# nixie_temp_clock.net
KiCad netlist of a schematic drawn in EAGLE
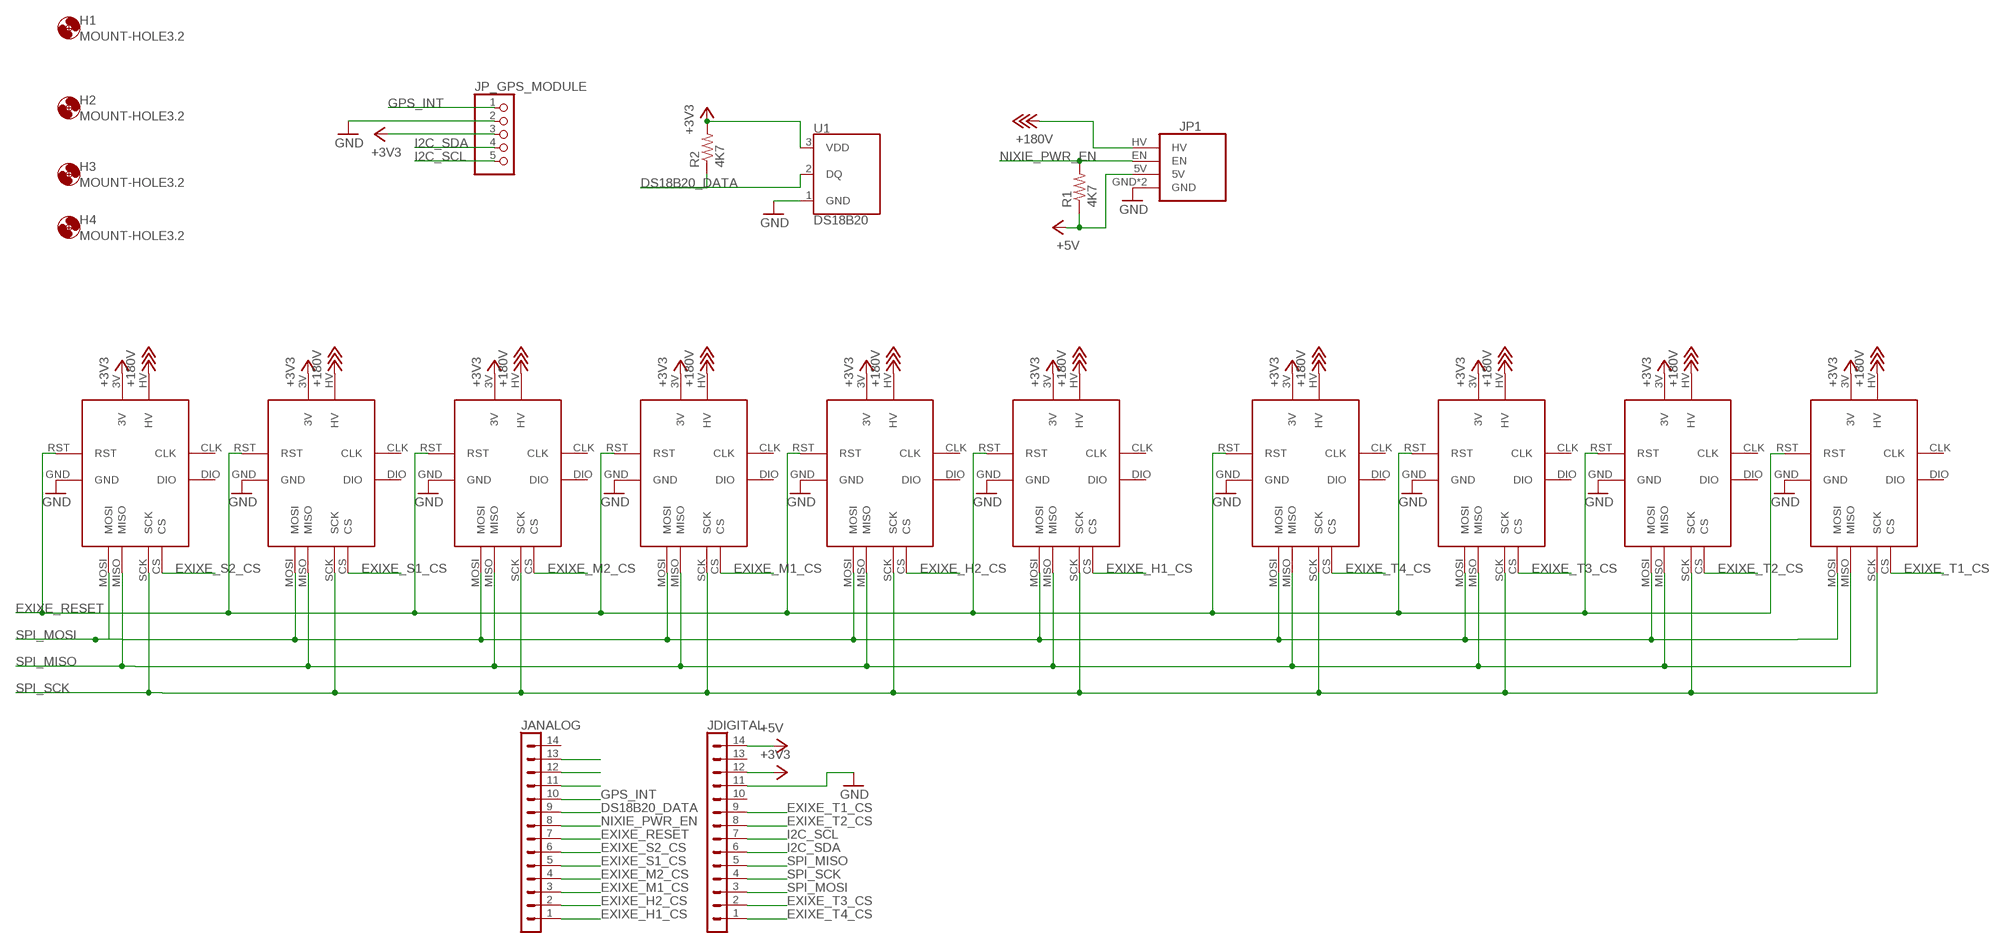
[diagram p0: schematic, sheet 1]

(export (version "E")
  (design (tool "Eeschema 10.0.6"))
  (components
    (comp (ref "EXIXE_H1")
      (value "EXIXE_MODULE_EXIXE")
      (footprint "eagle-import:EXIXE_MODULE_EXIXE_PAC")
      (libsource (lib "eagle-import") (part "EXIXE_MODULE_EXIXE"))
    )
    (comp (ref "EXIXE_H2")
      (value "EXIXE_MODULE_EXIXE")
      (footprint "eagle-import:EXIXE_MODULE_EXIXE_PAC")
      (libsource (lib "eagle-import") (part "EXIXE_MODULE_EXIXE"))
    )
    (comp (ref "EXIXE_M1")
      (value "EXIXE_MODULE_EXIXE")
      (footprint "eagle-import:EXIXE_MODULE_EXIXE_PAC")
      (libsource (lib "eagle-import") (part "EXIXE_MODULE_EXIXE"))
    )
    (comp (ref "EXIXE_M2")
      (value "EXIXE_MODULE_EXIXE")
      (footprint "eagle-import:EXIXE_MODULE_EXIXE_PAC")
      (libsource (lib "eagle-import") (part "EXIXE_MODULE_EXIXE"))
    )
    (comp (ref "EXIXE_S1")
      (value "EXIXE_MODULE_EXIXE")
      (footprint "eagle-import:EXIXE_MODULE_EXIXE_PAC")
      (libsource (lib "eagle-import") (part "EXIXE_MODULE_EXIXE"))
    )
    (comp (ref "EXIXE_S2")
      (value "EXIXE_MODULE_EXIXE")
      (footprint "eagle-import:EXIXE_MODULE_EXIXE_PAC")
      (libsource (lib "eagle-import") (part "EXIXE_MODULE_EXIXE"))
    )
    (comp (ref "EXIXE_T1")
      (value "EXIXE_MODULE_EXIXE")
      (footprint "eagle-import:EXIXE_MODULE_EXIXE_PAC")
      (libsource (lib "eagle-import") (part "EXIXE_MODULE_EXIXE"))
    )
    (comp (ref "EXIXE_T2")
      (value "EXIXE_MODULE_EXIXE")
      (footprint "eagle-import:EXIXE_MODULE_EXIXE_PAC")
      (libsource (lib "eagle-import") (part "EXIXE_MODULE_EXIXE"))
    )
    (comp (ref "EXIXE_T3")
      (value "EXIXE_MODULE_EXIXE")
      (footprint "eagle-import:EXIXE_MODULE_EXIXE_PAC")
      (libsource (lib "eagle-import") (part "EXIXE_MODULE_EXIXE"))
    )
    (comp (ref "EXIXE_T4")
      (value "EXIXE_MODULE_EXIXE")
      (footprint "eagle-import:EXIXE_MODULE_EXIXE_PAC")
      (libsource (lib "eagle-import") (part "EXIXE_MODULE_EXIXE"))
    )
    (comp (ref "H1")
      (value "MOUNT-HOLE3.2")
      (footprint "eagle-import:3,2")
      (libsource (lib "eagle-import") (part "MOUNT-HOLE3.2"))
    )
    (comp (ref "H2")
      (value "MOUNT-HOLE3.2")
      (footprint "eagle-import:3,2")
      (libsource (lib "eagle-import") (part "MOUNT-HOLE3.2"))
    )
    (comp (ref "H3")
      (value "MOUNT-HOLE3.2")
      (footprint "eagle-import:3,2")
      (libsource (lib "eagle-import") (part "MOUNT-HOLE3.2"))
    )
    (comp (ref "H4")
      (value "MOUNT-HOLE3.2")
      (footprint "eagle-import:3,2")
      (libsource (lib "eagle-import") (part "MOUNT-HOLE3.2"))
    )
    (comp (ref "JANALOG")
      (value "ARDUINO-CONNECTORS_PINHD-1X14-SMTH")
      (footprint "eagle-import:ARDUINO-CONNECTORS_1X14")
      (fields (field (name "MANUFACTURER") "ELDECO"))
      (libsource (lib "eagle-import") (part "ARDUINO-CONNECTORS_PINHD-1X14-SMTH"))
    )
    (comp (ref "JDIGITAL")
      (value "ARDUINO-CONNECTORS_PINHD-1X14-SMTH")
      (footprint "eagle-import:ARDUINO-CONNECTORS_1X14")
      (fields (field (name "MANUFACTURER") "ELDECO"))
      (libsource (lib "eagle-import") (part "ARDUINO-CONNECTORS_PINHD-1X14-SMTH"))
    )
    (comp (ref "JP1")
      (value "EBAY_MODULETAOBAO")
      (footprint "eagle-import:TAOBAO_PKG")
      (libsource (lib "eagle-import") (part "EBAY_MODULETAOBAO"))
    )
    (comp (ref "JP_GPS_MODULE")
      (value "PINHD-1X5")
      (footprint "eagle-import:1X05")
      (libsource (lib "eagle-import") (part "PINHD-1X5"))
    )
    (comp (ref "R1")
      (value "4K7")
      (footprint "eagle-import:0207_15")
      (libsource (lib "eagle-import") (part "R-US_0207/15"))
    )
    (comp (ref "R2")
      (value "4K7")
      (footprint "eagle-import:0207_15")
      (libsource (lib "eagle-import") (part "R-US_0207/15"))
    )
    (comp (ref "U1")
      (value "DS18B20")
      (footprint "eagle-import:TO-92-AMMO")
      (libsource (lib "eagle-import") (part "DS18B20"))
    )
  )
  (nets
    (net (code "1") (name "+3V3") (class "Default")
      (node (ref "EXIXE_H1") (pin "3V") (pinfunction "3V_3V") (pintype "bidirectional"))
      (node (ref "EXIXE_H2") (pin "3V") (pinfunction "3V_3V") (pintype "bidirectional"))
      (node (ref "EXIXE_M1") (pin "3V") (pinfunction "3V_3V") (pintype "bidirectional"))
      (node (ref "EXIXE_M2") (pin "3V") (pinfunction "3V_3V") (pintype "bidirectional"))
      (node (ref "EXIXE_S1") (pin "3V") (pinfunction "3V_3V") (pintype "bidirectional"))
      (node (ref "EXIXE_S2") (pin "3V") (pinfunction "3V_3V") (pintype "bidirectional"))
      (node (ref "EXIXE_T1") (pin "3V") (pinfunction "3V_3V") (pintype "bidirectional"))
      (node (ref "EXIXE_T2") (pin "3V") (pinfunction "3V_3V") (pintype "bidirectional"))
      (node (ref "EXIXE_T3") (pin "3V") (pinfunction "3V_3V") (pintype "bidirectional"))
      (node (ref "EXIXE_T4") (pin "3V") (pinfunction "3V_3V") (pintype "bidirectional"))
      (node (ref "JDIGITAL") (pin "12") (pinfunction "12_12") (pintype "passive"))
      (node (ref "JP_GPS_MODULE") (pin "3") (pinfunction "3_3") (pintype "passive"))
      (node (ref "R2") (pin "2") (pinfunction "2_2") (pintype "passive"))
      (node (ref "U1") (pin "3") (pinfunction "VDD_3") (pintype "power_in"))
    )
    (net (code "2") (name "+5V") (class "Default")
      (node (ref "JDIGITAL") (pin "14") (pinfunction "14_14") (pintype "passive"))
      (node (ref "JP1") (pin "5V") (pinfunction "5V_5V") (pintype "bidirectional"))
      (node (ref "R1") (pin "1") (pinfunction "1_1") (pintype "passive"))
    )
    (net (code "3") (name "+180V") (class "Default")
      (node (ref "EXIXE_H1") (pin "HV") (pinfunction "HV_HV") (pintype "bidirectional"))
      (node (ref "EXIXE_H2") (pin "HV") (pinfunction "HV_HV") (pintype "bidirectional"))
      (node (ref "EXIXE_M1") (pin "HV") (pinfunction "HV_HV") (pintype "bidirectional"))
      (node (ref "EXIXE_M2") (pin "HV") (pinfunction "HV_HV") (pintype "bidirectional"))
      (node (ref "EXIXE_S1") (pin "HV") (pinfunction "HV_HV") (pintype "bidirectional"))
      (node (ref "EXIXE_S2") (pin "HV") (pinfunction "HV_HV") (pintype "bidirectional"))
      (node (ref "EXIXE_T1") (pin "HV") (pinfunction "HV_HV") (pintype "bidirectional"))
      (node (ref "EXIXE_T2") (pin "HV") (pinfunction "HV_HV") (pintype "bidirectional"))
      (node (ref "EXIXE_T3") (pin "HV") (pinfunction "HV_HV") (pintype "bidirectional"))
      (node (ref "EXIXE_T4") (pin "HV") (pinfunction "HV_HV") (pintype "bidirectional"))
      (node (ref "JP1") (pin "HV") (pinfunction "HV_HV") (pintype "bidirectional"))
    )
    (net (code "4") (name "/DS18B20_DATA") (class "Default")
      (node (ref "JANALOG") (pin "9") (pinfunction "9_9") (pintype "passive"))
      (node (ref "R2") (pin "1") (pinfunction "1_1") (pintype "passive"))
      (node (ref "U1") (pin "2") (pinfunction "DQ_2") (pintype "bidirectional"))
    )
    (net (code "5") (name "/EXIXE_H1_CS") (class "Default")
      (node (ref "EXIXE_S2") (pin "CS") (pinfunction "CS_CS") (pintype "bidirectional"))
      (node (ref "JANALOG") (pin "1") (pinfunction "1_1") (pintype "passive"))
    )
    (net (code "6") (name "/EXIXE_H2_CS") (class "Default")
      (node (ref "EXIXE_S1") (pin "CS") (pinfunction "CS_CS") (pintype "bidirectional"))
      (node (ref "JANALOG") (pin "2") (pinfunction "2_2") (pintype "passive"))
    )
    (net (code "7") (name "/EXIXE_M1_CS") (class "Default")
      (node (ref "EXIXE_M2") (pin "CS") (pinfunction "CS_CS") (pintype "bidirectional"))
      (node (ref "JANALOG") (pin "3") (pinfunction "3_3") (pintype "passive"))
    )
    (net (code "8") (name "/EXIXE_M2_CS") (class "Default")
      (node (ref "EXIXE_M1") (pin "CS") (pinfunction "CS_CS") (pintype "bidirectional"))
      (node (ref "JANALOG") (pin "4") (pinfunction "4_4") (pintype "passive"))
    )
    (net (code "9") (name "/EXIXE_RESET") (class "Default")
      (node (ref "EXIXE_H1") (pin "RST") (pinfunction "RST_RST") (pintype "bidirectional"))
      (node (ref "EXIXE_H2") (pin "RST") (pinfunction "RST_RST") (pintype "bidirectional"))
      (node (ref "EXIXE_M1") (pin "RST") (pinfunction "RST_RST") (pintype "bidirectional"))
      (node (ref "EXIXE_M2") (pin "RST") (pinfunction "RST_RST") (pintype "bidirectional"))
      (node (ref "EXIXE_S1") (pin "RST") (pinfunction "RST_RST") (pintype "bidirectional"))
      (node (ref "EXIXE_S2") (pin "RST") (pinfunction "RST_RST") (pintype "bidirectional"))
      (node (ref "EXIXE_T1") (pin "RST") (pinfunction "RST_RST") (pintype "bidirectional"))
      (node (ref "EXIXE_T2") (pin "RST") (pinfunction "RST_RST") (pintype "bidirectional"))
      (node (ref "EXIXE_T3") (pin "RST") (pinfunction "RST_RST") (pintype "bidirectional"))
      (node (ref "EXIXE_T4") (pin "RST") (pinfunction "RST_RST") (pintype "bidirectional"))
      (node (ref "JANALOG") (pin "7") (pinfunction "7_7") (pintype "passive"))
    )
    (net (code "10") (name "/EXIXE_S1_CS") (class "Default")
      (node (ref "EXIXE_H2") (pin "CS") (pinfunction "CS_CS") (pintype "bidirectional"))
      (node (ref "JANALOG") (pin "5") (pinfunction "5_5") (pintype "passive"))
    )
    (net (code "11") (name "/EXIXE_S2_CS") (class "Default")
      (node (ref "EXIXE_H1") (pin "CS") (pinfunction "CS_CS") (pintype "bidirectional"))
      (node (ref "JANALOG") (pin "6") (pinfunction "6_6") (pintype "passive"))
    )
    (net (code "12") (name "/EXIXE_T1_CS") (class "Default")
      (node (ref "EXIXE_T4") (pin "CS") (pinfunction "CS_CS") (pintype "bidirectional"))
      (node (ref "JDIGITAL") (pin "9") (pinfunction "9_9") (pintype "passive"))
    )
    (net (code "13") (name "/EXIXE_T2_CS") (class "Default")
      (node (ref "EXIXE_T3") (pin "CS") (pinfunction "CS_CS") (pintype "bidirectional"))
      (node (ref "JDIGITAL") (pin "8") (pinfunction "8_8") (pintype "passive"))
    )
    (net (code "14") (name "/EXIXE_T3_CS") (class "Default")
      (node (ref "EXIXE_T2") (pin "CS") (pinfunction "CS_CS") (pintype "bidirectional"))
      (node (ref "JDIGITAL") (pin "2") (pinfunction "2_2") (pintype "passive"))
    )
    (net (code "15") (name "/EXIXE_T4_CS") (class "Default")
      (node (ref "EXIXE_T1") (pin "CS") (pinfunction "CS_CS") (pintype "bidirectional"))
      (node (ref "JDIGITAL") (pin "1") (pinfunction "1_1") (pintype "passive"))
    )
    (net (code "16") (name "/GPS_INT") (class "Default")
      (node (ref "JANALOG") (pin "10") (pinfunction "10_10") (pintype "passive"))
      (node (ref "JP_GPS_MODULE") (pin "1") (pinfunction "1_1") (pintype "passive"))
    )
    (net (code "17") (name "/I2C_SCL") (class "Default")
      (node (ref "JDIGITAL") (pin "7") (pinfunction "7_7") (pintype "passive"))
      (node (ref "JP_GPS_MODULE") (pin "5") (pinfunction "5_5") (pintype "passive"))
    )
    (net (code "18") (name "/I2C_SDA") (class "Default")
      (node (ref "JDIGITAL") (pin "6") (pinfunction "6_6") (pintype "passive"))
      (node (ref "JP_GPS_MODULE") (pin "4") (pinfunction "4_4") (pintype "passive"))
    )
    (net (code "19") (name "/NIXIE_PWR_EN") (class "Default")
      (node (ref "JANALOG") (pin "8") (pinfunction "8_8") (pintype "passive"))
      (node (ref "JP1") (pin "EN") (pinfunction "EN_EN") (pintype "bidirectional"))
      (node (ref "R1") (pin "2") (pinfunction "2_2") (pintype "passive"))
    )
    (net (code "20") (name "/SPI_MISO") (class "Default")
      (node (ref "EXIXE_H1") (pin "MISO") (pinfunction "MISO_MISO") (pintype "bidirectional"))
      (node (ref "EXIXE_H2") (pin "MISO") (pinfunction "MISO_MISO") (pintype "bidirectional"))
      (node (ref "EXIXE_M1") (pin "MISO") (pinfunction "MISO_MISO") (pintype "bidirectional"))
      (node (ref "EXIXE_M2") (pin "MISO") (pinfunction "MISO_MISO") (pintype "bidirectional"))
      (node (ref "EXIXE_S1") (pin "MISO") (pinfunction "MISO_MISO") (pintype "bidirectional"))
      (node (ref "EXIXE_S2") (pin "MISO") (pinfunction "MISO_MISO") (pintype "bidirectional"))
      (node (ref "EXIXE_T1") (pin "MISO") (pinfunction "MISO_MISO") (pintype "bidirectional"))
      (node (ref "EXIXE_T2") (pin "MISO") (pinfunction "MISO_MISO") (pintype "bidirectional"))
      (node (ref "EXIXE_T3") (pin "MISO") (pinfunction "MISO_MISO") (pintype "bidirectional"))
      (node (ref "EXIXE_T4") (pin "MISO") (pinfunction "MISO_MISO") (pintype "bidirectional"))
      (node (ref "JDIGITAL") (pin "5") (pinfunction "5_5") (pintype "passive"))
    )
    (net (code "21") (name "/SPI_MOSI") (class "Default")
      (node (ref "EXIXE_H1") (pin "MOSI") (pinfunction "MOSI_MOSI") (pintype "bidirectional"))
      (node (ref "EXIXE_H2") (pin "MOSI") (pinfunction "MOSI_MOSI") (pintype "bidirectional"))
      (node (ref "EXIXE_M1") (pin "MOSI") (pinfunction "MOSI_MOSI") (pintype "bidirectional"))
      (node (ref "EXIXE_M2") (pin "MOSI") (pinfunction "MOSI_MOSI") (pintype "bidirectional"))
      (node (ref "EXIXE_S1") (pin "MOSI") (pinfunction "MOSI_MOSI") (pintype "bidirectional"))
      (node (ref "EXIXE_S2") (pin "MOSI") (pinfunction "MOSI_MOSI") (pintype "bidirectional"))
      (node (ref "EXIXE_T1") (pin "MOSI") (pinfunction "MOSI_MOSI") (pintype "bidirectional"))
      (node (ref "EXIXE_T2") (pin "MOSI") (pinfunction "MOSI_MOSI") (pintype "bidirectional"))
      (node (ref "EXIXE_T3") (pin "MOSI") (pinfunction "MOSI_MOSI") (pintype "bidirectional"))
      (node (ref "EXIXE_T4") (pin "MOSI") (pinfunction "MOSI_MOSI") (pintype "bidirectional"))
      (node (ref "JDIGITAL") (pin "3") (pinfunction "3_3") (pintype "passive"))
    )
    (net (code "22") (name "/SPI_SCK") (class "Default")
      (node (ref "EXIXE_H1") (pin "SCK") (pinfunction "SCK_SCK") (pintype "bidirectional"))
      (node (ref "EXIXE_H2") (pin "SCK") (pinfunction "SCK_SCK") (pintype "bidirectional"))
      (node (ref "EXIXE_M1") (pin "SCK") (pinfunction "SCK_SCK") (pintype "bidirectional"))
      (node (ref "EXIXE_M2") (pin "SCK") (pinfunction "SCK_SCK") (pintype "bidirectional"))
      (node (ref "EXIXE_S1") (pin "SCK") (pinfunction "SCK_SCK") (pintype "bidirectional"))
      (node (ref "EXIXE_S2") (pin "SCK") (pinfunction "SCK_SCK") (pintype "bidirectional"))
      (node (ref "EXIXE_T1") (pin "SCK") (pinfunction "SCK_SCK") (pintype "bidirectional"))
      (node (ref "EXIXE_T2") (pin "SCK") (pinfunction "SCK_SCK") (pintype "bidirectional"))
      (node (ref "EXIXE_T3") (pin "SCK") (pinfunction "SCK_SCK") (pintype "bidirectional"))
      (node (ref "EXIXE_T4") (pin "SCK") (pinfunction "SCK_SCK") (pintype "bidirectional"))
      (node (ref "JDIGITAL") (pin "4") (pinfunction "4_4") (pintype "passive"))
    )
    (net (code "23") (name "GND") (class "Default")
      (node (ref "EXIXE_H1") (pin "GND") (pinfunction "GND_GND") (pintype "bidirectional"))
      (node (ref "EXIXE_H2") (pin "GND") (pinfunction "GND_GND") (pintype "bidirectional"))
      (node (ref "EXIXE_M1") (pin "GND") (pinfunction "GND_GND") (pintype "bidirectional"))
      (node (ref "EXIXE_M2") (pin "GND") (pinfunction "GND_GND") (pintype "bidirectional"))
      (node (ref "EXIXE_S1") (pin "GND") (pinfunction "GND_GND") (pintype "bidirectional"))
      (node (ref "EXIXE_S2") (pin "GND") (pinfunction "GND_GND") (pintype "bidirectional"))
      (node (ref "EXIXE_T1") (pin "GND") (pinfunction "GND_GND") (pintype "bidirectional"))
      (node (ref "EXIXE_T2") (pin "GND") (pinfunction "GND_GND") (pintype "bidirectional"))
      (node (ref "EXIXE_T3") (pin "GND") (pinfunction "GND_GND") (pintype "bidirectional"))
      (node (ref "EXIXE_T4") (pin "GND") (pinfunction "GND_GND") (pintype "bidirectional"))
      (node (ref "JDIGITAL") (pin "11") (pinfunction "11_11") (pintype "passive"))
      (node (ref "JP1") (pin "GND") (pinfunction "GND_GND") (pintype "bidirectional"))
      (node (ref "JP1") (pin "GND2") (pinfunction "GND_GND2") (pintype "bidirectional"))
      (node (ref "JP_GPS_MODULE") (pin "2") (pinfunction "2_2") (pintype "passive"))
      (node (ref "U1") (pin "1") (pinfunction "GND_1") (pintype "power_in"))
    )
    (net (code "24") (name "unconnected-(EXIXE_H1-PadCLK)") (class "Default")
      (node (ref "EXIXE_H1") (pin "CLK") (pinfunction "CLK_CLK") (pintype "bidirectional"))
    )
    (net (code "25") (name "unconnected-(EXIXE_H1-PadDIO)") (class "Default")
      (node (ref "EXIXE_H1") (pin "DIO") (pinfunction "DIO_DIO") (pintype "bidirectional"))
    )
    (net (code "26") (name "unconnected-(EXIXE_H2-PadCLK)") (class "Default")
      (node (ref "EXIXE_H2") (pin "CLK") (pinfunction "CLK_CLK") (pintype "bidirectional"))
    )
    (net (code "27") (name "unconnected-(EXIXE_H2-PadDIO)") (class "Default")
      (node (ref "EXIXE_H2") (pin "DIO") (pinfunction "DIO_DIO") (pintype "bidirectional"))
    )
    (net (code "28") (name "unconnected-(EXIXE_M1-PadCLK)") (class "Default")
      (node (ref "EXIXE_M1") (pin "CLK") (pinfunction "CLK_CLK") (pintype "bidirectional"))
    )
    (net (code "29") (name "unconnected-(EXIXE_M1-PadDIO)") (class "Default")
      (node (ref "EXIXE_M1") (pin "DIO") (pinfunction "DIO_DIO") (pintype "bidirectional"))
    )
    (net (code "30") (name "unconnected-(EXIXE_M2-PadCLK)") (class "Default")
      (node (ref "EXIXE_M2") (pin "CLK") (pinfunction "CLK_CLK") (pintype "bidirectional"))
    )
    (net (code "31") (name "unconnected-(EXIXE_M2-PadDIO)") (class "Default")
      (node (ref "EXIXE_M2") (pin "DIO") (pinfunction "DIO_DIO") (pintype "bidirectional"))
    )
    (net (code "32") (name "unconnected-(EXIXE_S1-PadCLK)") (class "Default")
      (node (ref "EXIXE_S1") (pin "CLK") (pinfunction "CLK_CLK") (pintype "bidirectional"))
    )
    (net (code "33") (name "unconnected-(EXIXE_S1-PadDIO)") (class "Default")
      (node (ref "EXIXE_S1") (pin "DIO") (pinfunction "DIO_DIO") (pintype "bidirectional"))
    )
    (net (code "34") (name "unconnected-(EXIXE_S2-PadCLK)") (class "Default")
      (node (ref "EXIXE_S2") (pin "CLK") (pinfunction "CLK_CLK") (pintype "bidirectional"))
    )
    (net (code "35") (name "unconnected-(EXIXE_S2-PadDIO)") (class "Default")
      (node (ref "EXIXE_S2") (pin "DIO") (pinfunction "DIO_DIO") (pintype "bidirectional"))
    )
    (net (code "36") (name "unconnected-(EXIXE_T1-PadCLK)") (class "Default")
      (node (ref "EXIXE_T1") (pin "CLK") (pinfunction "CLK_CLK") (pintype "bidirectional"))
    )
    (net (code "37") (name "unconnected-(EXIXE_T1-PadDIO)") (class "Default")
      (node (ref "EXIXE_T1") (pin "DIO") (pinfunction "DIO_DIO") (pintype "bidirectional"))
    )
    (net (code "38") (name "unconnected-(EXIXE_T2-PadCLK)") (class "Default")
      (node (ref "EXIXE_T2") (pin "CLK") (pinfunction "CLK_CLK") (pintype "bidirectional"))
    )
    (net (code "39") (name "unconnected-(EXIXE_T2-PadDIO)") (class "Default")
      (node (ref "EXIXE_T2") (pin "DIO") (pinfunction "DIO_DIO") (pintype "bidirectional"))
    )
    (net (code "40") (name "unconnected-(EXIXE_T3-PadCLK)") (class "Default")
      (node (ref "EXIXE_T3") (pin "CLK") (pinfunction "CLK_CLK") (pintype "bidirectional"))
    )
    (net (code "41") (name "unconnected-(EXIXE_T3-PadDIO)") (class "Default")
      (node (ref "EXIXE_T3") (pin "DIO") (pinfunction "DIO_DIO") (pintype "bidirectional"))
    )
    (net (code "42") (name "unconnected-(EXIXE_T4-PadCLK)") (class "Default")
      (node (ref "EXIXE_T4") (pin "CLK") (pinfunction "CLK_CLK") (pintype "bidirectional"))
    )
    (net (code "43") (name "unconnected-(EXIXE_T4-PadDIO)") (class "Default")
      (node (ref "EXIXE_T4") (pin "DIO") (pinfunction "DIO_DIO") (pintype "bidirectional"))
    )
    (net (code "44") (name "unconnected-(JANALOG-Pad11)") (class "Default")
      (node (ref "JANALOG") (pin "11") (pinfunction "11_11") (pintype "passive"))
    )
    (net (code "45") (name "unconnected-(JANALOG-Pad12)") (class "Default")
      (node (ref "JANALOG") (pin "12") (pinfunction "12_12") (pintype "passive"))
    )
    (net (code "46") (name "unconnected-(JANALOG-Pad13)") (class "Default")
      (node (ref "JANALOG") (pin "13") (pinfunction "13_13") (pintype "passive"))
    )
    (net (code "47") (name "unconnected-(JANALOG-Pad14)") (class "Default")
      (node (ref "JANALOG") (pin "14") (pinfunction "14_14") (pintype "passive"))
    )
    (net (code "48") (name "unconnected-(JDIGITAL-Pad10)") (class "Default")
      (node (ref "JDIGITAL") (pin "10") (pinfunction "10_10") (pintype "passive"))
    )
    (net (code "49") (name "unconnected-(JDIGITAL-Pad13)") (class "Default")
      (node (ref "JDIGITAL") (pin "13") (pinfunction "13_13") (pintype "passive"))
    )
  )
)
